# V01.net
KiCad netlist of a schematic drawn in EAGLE
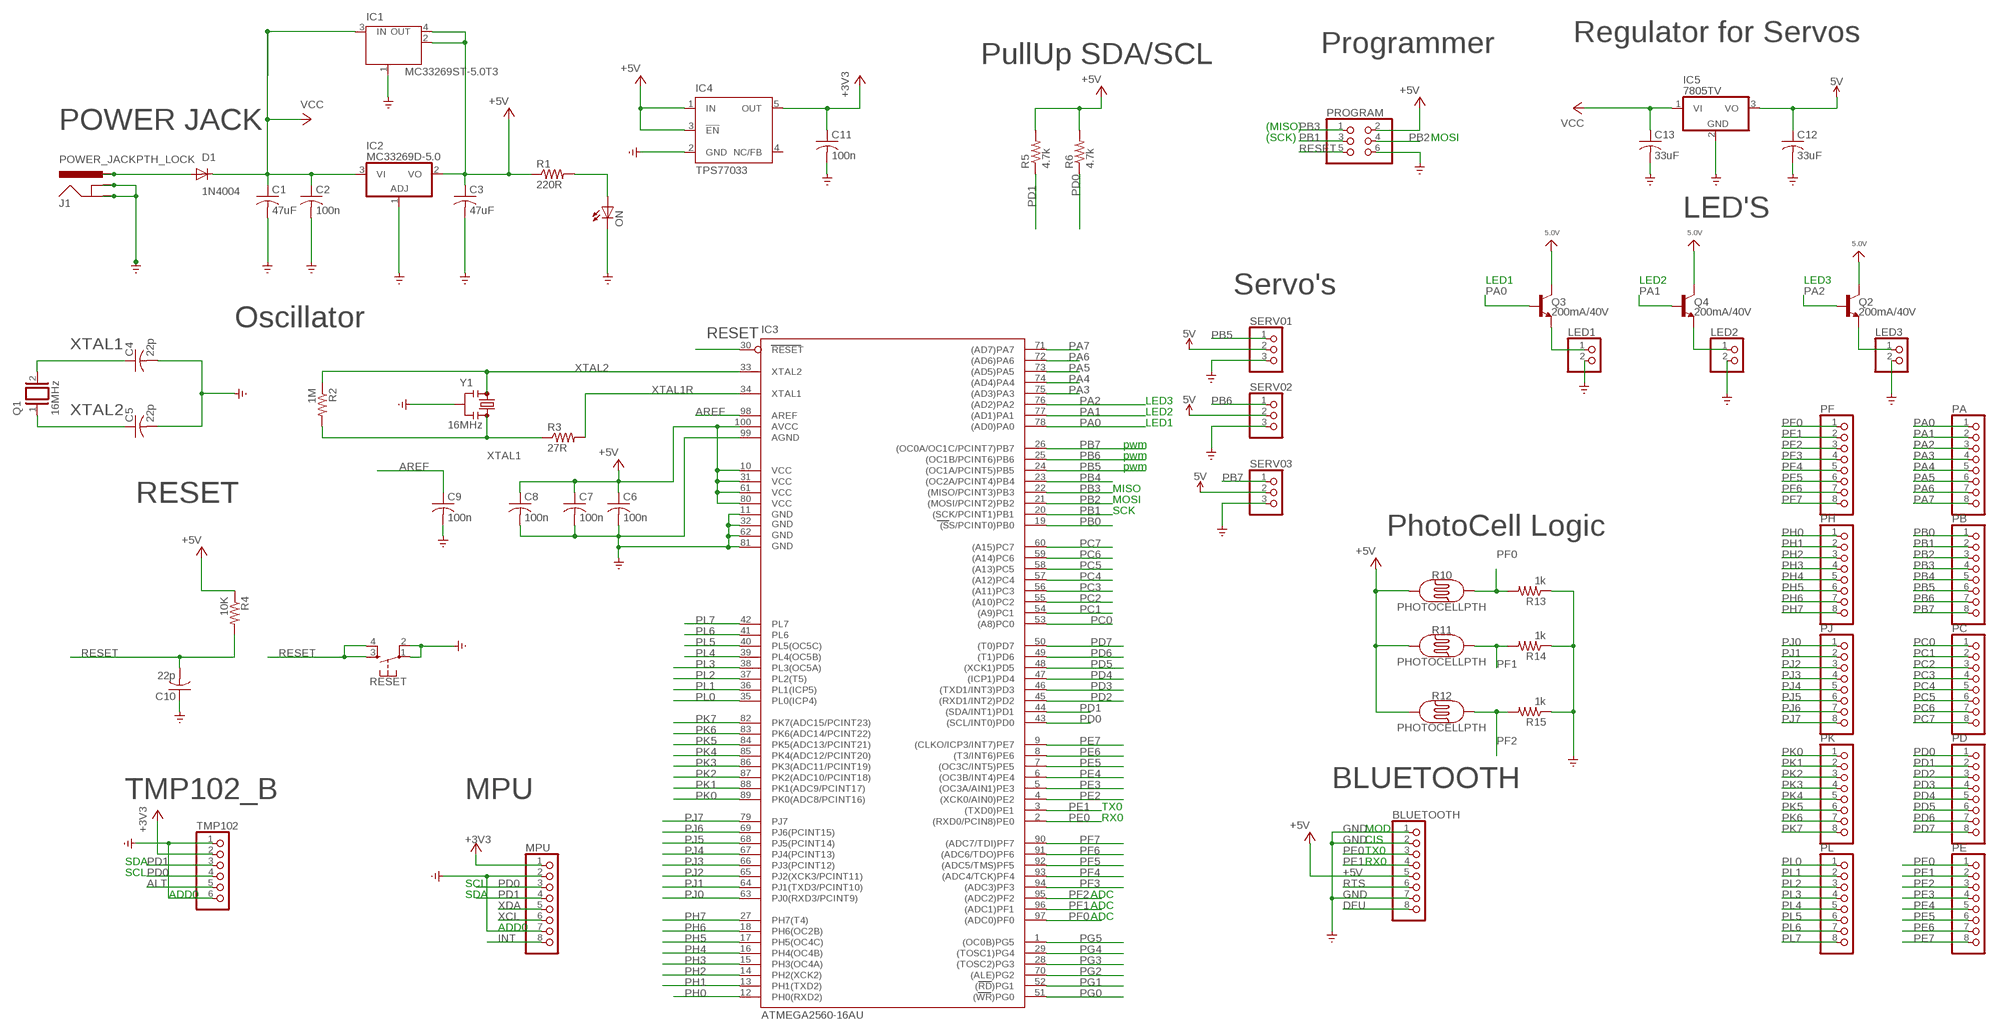
[diagram p0: schematic, sheet 1, part 1 of 2]
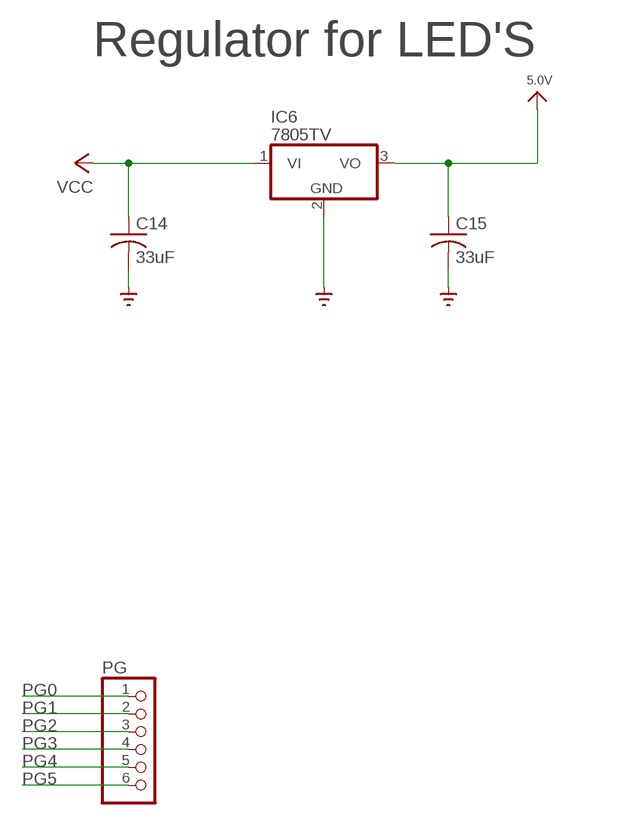
[diagram p1: schematic, sheet 1, part 2 of 2]

(export (version "E")
  (design (tool "Eeschema 10.0.6"))
  (components
    (comp (ref "BLUETOOTH")
      (value "PINHD-1X8")
      (footprint "eagle-import:1X08")
      (libsource (lib "eagle-import") (part "PINHD-1X8"))
    )
    (comp (ref "C1")
      (value "47uF")
      (footprint "eagle-import:C025-024X044")
      (libsource (lib "eagle-import") (part "C-US025-024X044"))
    )
    (comp (ref "C2")
      (value "100n")
      (footprint "eagle-import:C025-024X044")
      (libsource (lib "eagle-import") (part "C-US025-024X044"))
    )
    (comp (ref "C3")
      (value "47uF")
      (footprint "eagle-import:C025-024X044")
      (libsource (lib "eagle-import") (part "C-US025-024X044"))
    )
    (comp (ref "C4")
      (value "22p")
      (footprint "eagle-import:C025-024X044")
      (libsource (lib "eagle-import") (part "C-US025-024X044"))
    )
    (comp (ref "C5")
      (value "22p")
      (footprint "eagle-import:C025-024X044")
      (libsource (lib "eagle-import") (part "C-US025-024X044"))
    )
    (comp (ref "C6")
      (value "100n")
      (footprint "eagle-import:C025-024X044")
      (libsource (lib "eagle-import") (part "C-US025-024X044"))
    )
    (comp (ref "C7")
      (value "100n")
      (footprint "eagle-import:C025-024X044")
      (libsource (lib "eagle-import") (part "C-US025-024X044"))
    )
    (comp (ref "C8")
      (value "100n")
      (footprint "eagle-import:C025-024X044")
      (libsource (lib "eagle-import") (part "C-US025-024X044"))
    )
    (comp (ref "C9")
      (value "100n")
      (footprint "eagle-import:C025-024X044")
      (libsource (lib "eagle-import") (part "C-US025-024X044"))
    )
    (comp (ref "C10")
      (value "22p")
      (footprint "eagle-import:C025-024X044")
      (libsource (lib "eagle-import") (part "C-US025-024X044"))
    )
    (comp (ref "C11")
      (value "100n")
      (footprint "eagle-import:C025-024X044")
      (libsource (lib "eagle-import") (part "C-US025-024X044"))
    )
    (comp (ref "C12")
      (value "33uF")
      (footprint "eagle-import:C025-024X044")
      (libsource (lib "eagle-import") (part "C-US025-024X044"))
    )
    (comp (ref "C13")
      (value "33uF")
      (footprint "eagle-import:C025-024X044")
      (libsource (lib "eagle-import") (part "C-US025-024X044"))
    )
    (comp (ref "C14")
      (value "33uF")
      (footprint "eagle-import:C025-024X044")
      (libsource (lib "eagle-import") (part "C-US025-024X044"))
    )
    (comp (ref "C15")
      (value "33uF")
      (footprint "eagle-import:C025-024X044")
      (libsource (lib "eagle-import") (part "C-US025-024X044"))
    )
    (comp (ref "D1")
      (value "1N4004")
      (footprint "eagle-import:DO41-10")
      (libsource (lib "eagle-import") (part "1N4004"))
    )
    (comp (ref "IC1")
      (value "MC33269ST-5.0T3")
      (footprint "eagle-import:SOT223")
      (libsource (lib "eagle-import") (part "MC33269ST-3.3T3"))
    )
    (comp (ref "IC2")
      (value "MC33269D-5.0")
      (footprint "eagle-import:DPACK")
      (libsource (lib "eagle-import") (part "MC33269?D-5.0"))
    )
    (comp (ref "IC3")
      (value "ATMEGA2560-16AU")
      (footprint "eagle-import:TQFP100")
      (libsource (lib "eagle-import") (part "ATMEGAAU2560-16"))
    )
    (comp (ref "IC4")
      (value "TPS77033")
      (footprint "eagle-import:SOT23-DBV")
      (fields (field (name "MF") "TEXAS INSTRUMENTS") (field (name "MPN") "TPS77033DBVT"))
      (libsource (lib "eagle-import") (part "TPS77033"))
    )
    (comp (ref "IC5")
      (value "7805TV")
      (footprint "eagle-import:TO220V")
      (libsource (lib "eagle-import") (part "78TV05"))
    )
    (comp (ref "IC6")
      (value "7805TV")
      (footprint "eagle-import:TO220V")
      (libsource (lib "eagle-import") (part "78TV05"))
    )
    (comp (ref "J1")
      (value "POWER_JACKPTH_LOCK")
      (footprint "eagle-import:POWER_JACK_PTH_LOCK")
      (libsource (lib "eagle-import") (part "POWER_JACKPTH_LOCK"))
    )
    (comp (ref "LED1")
      (value "PINHD-1X2")
      (footprint "eagle-import:1X02")
      (libsource (lib "eagle-import") (part "PINHD-1X2"))
    )
    (comp (ref "LED2")
      (value "PINHD-1X2")
      (footprint "eagle-import:1X02")
      (libsource (lib "eagle-import") (part "PINHD-1X2"))
    )
    (comp (ref "LED3")
      (value "PINHD-1X2")
      (footprint "eagle-import:1X02")
      (libsource (lib "eagle-import") (part "PINHD-1X2"))
    )
    (comp (ref "MPU")
      (value "PINHD-1X8")
      (footprint "eagle-import:1X08")
      (libsource (lib "eagle-import") (part "PINHD-1X8"))
    )
    (comp (ref "ON")
      (value "LED3MM")
      (footprint "eagle-import:LED3MM")
      (libsource (lib "eagle-import") (part "LED3MM"))
    )
    (comp (ref "PA")
      (value "PINHD-1X8")
      (footprint "eagle-import:1X08")
      (libsource (lib "eagle-import") (part "PINHD-1X8"))
    )
    (comp (ref "PB")
      (value "PINHD-1X8")
      (footprint "eagle-import:1X08")
      (libsource (lib "eagle-import") (part "PINHD-1X8"))
    )
    (comp (ref "PC")
      (value "PINHD-1X8")
      (footprint "eagle-import:1X08")
      (libsource (lib "eagle-import") (part "PINHD-1X8"))
    )
    (comp (ref "PD")
      (value "PINHD-1X8")
      (footprint "eagle-import:1X08")
      (libsource (lib "eagle-import") (part "PINHD-1X8"))
    )
    (comp (ref "PE")
      (value "PINHD-1X8")
      (footprint "eagle-import:1X08")
      (libsource (lib "eagle-import") (part "PINHD-1X8"))
    )
    (comp (ref "PF")
      (value "PINHD-1X8")
      (footprint "eagle-import:1X08")
      (libsource (lib "eagle-import") (part "PINHD-1X8"))
    )
    (comp (ref "PG")
      (value "PINHD-1X6")
      (footprint "eagle-import:1X06")
      (libsource (lib "eagle-import") (part "PINHD-1X6"))
    )
    (comp (ref "PH")
      (value "PINHD-1X8")
      (footprint "eagle-import:1X08")
      (libsource (lib "eagle-import") (part "PINHD-1X8"))
    )
    (comp (ref "PJ")
      (value "PINHD-1X8")
      (footprint "eagle-import:1X08")
      (libsource (lib "eagle-import") (part "PINHD-1X8"))
    )
    (comp (ref "PK")
      (value "PINHD-1X8")
      (footprint "eagle-import:1X08")
      (libsource (lib "eagle-import") (part "PINHD-1X8"))
    )
    (comp (ref "PL")
      (value "PINHD-1X8")
      (footprint "eagle-import:1X08")
      (libsource (lib "eagle-import") (part "PINHD-1X8"))
    )
    (comp (ref "PROGRAM")
      (value "PINHD-2X3")
      (footprint "eagle-import:2X03")
      (libsource (lib "eagle-import") (part "PINHD-2X3"))
    )
    (comp (ref "Q1")
      (value "16MHz")
      (footprint "eagle-import:QS")
      (libsource (lib "eagle-import") (part "XTAL/S"))
    )
    (comp (ref "Q2")
      (value "200mA/40V")
      (footprint "eagle-import:TO-92")
      (libsource (lib "eagle-import") (part "TRANS_NPN-2N3904"))
    )
    (comp (ref "Q3")
      (value "200mA/40V")
      (footprint "eagle-import:TO-92")
      (libsource (lib "eagle-import") (part "TRANS_NPN-2N3904"))
    )
    (comp (ref "Q4")
      (value "200mA/40V")
      (footprint "eagle-import:TO-92")
      (libsource (lib "eagle-import") (part "TRANS_NPN-2N3904"))
    )
    (comp (ref "R1")
      (value "220R")
      (footprint "eagle-import:0204V")
      (libsource (lib "eagle-import") (part "R-US_0204/2V"))
    )
    (comp (ref "R2")
      (value "1M")
      (footprint "eagle-import:0204V")
      (libsource (lib "eagle-import") (part "R-US_0204/2V"))
    )
    (comp (ref "R3")
      (value "27R")
      (footprint "eagle-import:0204V")
      (libsource (lib "eagle-import") (part "R-US_0204/2V"))
    )
    (comp (ref "R4")
      (value "10K")
      (footprint "eagle-import:0204V")
      (libsource (lib "eagle-import") (part "R-US_0204/2V"))
    )
    (comp (ref "R5")
      (value "4.7k")
      (footprint "eagle-import:0204V")
      (libsource (lib "eagle-import") (part "R-US_0204/2V"))
    )
    (comp (ref "R6")
      (value "4.7k")
      (footprint "eagle-import:0204V")
      (libsource (lib "eagle-import") (part "R-US_0204/2V"))
    )
    (comp (ref "R10")
      (value "PHOTOCELLPTH")
      (footprint "eagle-import:PHOTOCELL")
      (libsource (lib "eagle-import") (part "PHOTOCELLPTH"))
    )
    (comp (ref "R11")
      (value "PHOTOCELLPTH")
      (footprint "eagle-import:PHOTOCELL")
      (libsource (lib "eagle-import") (part "PHOTOCELLPTH"))
    )
    (comp (ref "R12")
      (value "PHOTOCELLPTH")
      (footprint "eagle-import:PHOTOCELL")
      (libsource (lib "eagle-import") (part "PHOTOCELLPTH"))
    )
    (comp (ref "R13")
      (value "1k")
      (footprint "eagle-import:0204V")
      (libsource (lib "eagle-import") (part "R-US_0204/2V"))
    )
    (comp (ref "R14")
      (value "1k")
      (footprint "eagle-import:0204V")
      (libsource (lib "eagle-import") (part "R-US_0204/2V"))
    )
    (comp (ref "R15")
      (value "1k")
      (footprint "eagle-import:0204V")
      (libsource (lib "eagle-import") (part "R-US_0204/2V"))
    )
    (comp (ref "RESET")
      (value "MOMENTARY-SWITCH-SPST-2-SMD-5.2MM")
      (footprint "eagle-import:TACTILE_SWITCH_SMD_5.2MM")
      (libsource (lib "eagle-import") (part "MOMENTARY-SWITCH-SPST-2-SMD-5.2MM"))
    )
    (comp (ref "SERV01")
      (value "PINHD-1X3")
      (footprint "eagle-import:1X03")
      (libsource (lib "eagle-import") (part "PINHD-1X3"))
    )
    (comp (ref "SERV02")
      (value "PINHD-1X3")
      (footprint "eagle-import:1X03")
      (libsource (lib "eagle-import") (part "PINHD-1X3"))
    )
    (comp (ref "SERV03")
      (value "PINHD-1X3")
      (footprint "eagle-import:1X03")
      (libsource (lib "eagle-import") (part "PINHD-1X3"))
    )
    (comp (ref "TMP102")
      (value "PINHD-1X6")
      (footprint "eagle-import:1X06")
      (libsource (lib "eagle-import") (part "PINHD-1X6"))
    )
    (comp (ref "Y1")
      (value "16MHz")
      (footprint "eagle-import:RESONATOR-SMD-3.2X1.3")
      (libsource (lib "eagle-import") (part "RESONATORSMD-3.2X1.3"))
    )
  )
  (nets
    (net (code "1") (name "+3V3") (class "Default")
      (node (ref "C11") (pin "1") (pinfunction "1_1") (pintype "passive"))
      (node (ref "IC4") (pin "5") (pinfunction "OUT_5") (pintype "passive"))
      (node (ref "MPU") (pin "1") (pinfunction "1_1") (pintype "passive"))
      (node (ref "TMP102") (pin "2") (pinfunction "2_2") (pintype "passive"))
    )
    (net (code "2") (name "+5V") (class "Default")
      (node (ref "BLUETOOTH") (pin "5") (pinfunction "5_5") (pintype "passive"))
      (node (ref "C3") (pin "1") (pinfunction "1_1") (pintype "passive"))
      (node (ref "C6") (pin "1") (pinfunction "1_1") (pintype "passive"))
      (node (ref "C7") (pin "1") (pinfunction "1_1") (pintype "passive"))
      (node (ref "C8") (pin "1") (pinfunction "1_1") (pintype "passive"))
      (node (ref "IC1") (pin "2") (pinfunction "OUT_2") (pintype "passive"))
      (node (ref "IC1") (pin "4") (pinfunction "OUT_4") (pintype "passive"))
      (node (ref "IC2") (pin "2") (pinfunction "VO_2") (pintype "passive"))
      (node (ref "IC3") (pin "10") (pinfunction "VCC_10") (pintype "power_in"))
      (node (ref "IC3") (pin "100") (pinfunction "AVCC_100") (pintype "power_in"))
      (node (ref "IC3") (pin "31") (pinfunction "VCC1_31") (pintype "power_in"))
      (node (ref "IC3") (pin "61") (pinfunction "VCC2_61") (pintype "power_in"))
      (node (ref "IC3") (pin "80") (pinfunction "VCC3_80") (pintype "power_in"))
      (node (ref "IC4") (pin "1") (pinfunction "IN_1") (pintype "input"))
      (node (ref "IC4") (pin "3") (pinfunction "~{EN}_3") (pintype "input"))
      (node (ref "PROGRAM") (pin "2") (pinfunction "2_2") (pintype "passive"))
      (node (ref "R1") (pin "1") (pinfunction "1_1") (pintype "passive"))
      (node (ref "R10") (pin "1") (pinfunction "P$1_1") (pintype "bidirectional"))
      (node (ref "R11") (pin "1") (pinfunction "P$1_1") (pintype "bidirectional"))
      (node (ref "R12") (pin "1") (pinfunction "P$1_1") (pintype "bidirectional"))
      (node (ref "R4") (pin "1") (pinfunction "1_1") (pintype "passive"))
      (node (ref "R5") (pin "2") (pinfunction "2_2") (pintype "passive"))
      (node (ref "R6") (pin "2") (pinfunction "2_2") (pintype "passive"))
    )
    (net (code "3") (name "/ALT") (class "Default")
      (node (ref "TMP102") (pin "5") (pinfunction "5_5") (pintype "passive"))
    )
    (net (code "4") (name "/AREF") (class "Default")
      (node (ref "C9") (pin "1") (pinfunction "1_1") (pintype "passive"))
      (node (ref "IC3") (pin "98") (pinfunction "AREF_98") (pintype "bidirectional"))
    )
    (net (code "5") (name "/DFU") (class "Default")
      (node (ref "BLUETOOTH") (pin "8") (pinfunction "8_8") (pintype "passive"))
    )
    (net (code "6") (name "/INT") (class "Default")
      (node (ref "MPU") (pin "8") (pinfunction "8_8") (pintype "passive"))
    )
    (net (code "7") (name "/PA0") (class "Default")
      (node (ref "IC3") (pin "78") (pinfunction "(AD0)PA0_78") (pintype "bidirectional"))
      (node (ref "PA") (pin "1") (pinfunction "1_1") (pintype "passive"))
      (node (ref "Q3") (pin "2") (pinfunction "B_2") (pintype "passive"))
    )
    (net (code "8") (name "/PA1") (class "Default")
      (node (ref "IC3") (pin "77") (pinfunction "(AD1)PA1_77") (pintype "bidirectional"))
      (node (ref "PA") (pin "2") (pinfunction "2_2") (pintype "passive"))
      (node (ref "Q4") (pin "2") (pinfunction "B_2") (pintype "passive"))
    )
    (net (code "9") (name "/PA2") (class "Default")
      (node (ref "IC3") (pin "76") (pinfunction "(AD2)PA2_76") (pintype "bidirectional"))
      (node (ref "PA") (pin "3") (pinfunction "3_3") (pintype "passive"))
      (node (ref "Q2") (pin "2") (pinfunction "B_2") (pintype "passive"))
    )
    (net (code "10") (name "/PA3") (class "Default")
      (node (ref "IC3") (pin "75") (pinfunction "(AD3)PA3_75") (pintype "bidirectional"))
      (node (ref "PA") (pin "4") (pinfunction "4_4") (pintype "passive"))
    )
    (net (code "11") (name "/PA4") (class "Default")
      (node (ref "IC3") (pin "74") (pinfunction "(AD4)PA4_74") (pintype "bidirectional"))
      (node (ref "PA") (pin "5") (pinfunction "5_5") (pintype "passive"))
    )
    (net (code "12") (name "/PA5") (class "Default")
      (node (ref "IC3") (pin "73") (pinfunction "(AD5)PA5_73") (pintype "bidirectional"))
      (node (ref "PA") (pin "6") (pinfunction "6_6") (pintype "passive"))
    )
    (net (code "13") (name "/PA6") (class "Default")
      (node (ref "IC3") (pin "72") (pinfunction "(AD6)PA6_72") (pintype "bidirectional"))
      (node (ref "PA") (pin "7") (pinfunction "7_7") (pintype "passive"))
    )
    (net (code "14") (name "/PA7") (class "Default")
      (node (ref "IC3") (pin "71") (pinfunction "(AD7)PA7_71") (pintype "bidirectional"))
      (node (ref "PA") (pin "8") (pinfunction "8_8") (pintype "passive"))
    )
    (net (code "15") (name "/PB0") (class "Default")
      (node (ref "IC3") (pin "19") (pinfunction "(SS/PCINT0)PB0_19") (pintype "bidirectional"))
      (node (ref "PB") (pin "1") (pinfunction "1_1") (pintype "passive"))
    )
    (net (code "16") (name "/PB1") (class "Default")
      (node (ref "IC3") (pin "20") (pinfunction "(SCK/PCINT1)PB1_20") (pintype "bidirectional"))
      (node (ref "PB") (pin "2") (pinfunction "2_2") (pintype "passive"))
      (node (ref "PROGRAM") (pin "3") (pinfunction "3_3") (pintype "passive"))
    )
    (net (code "17") (name "/PB2") (class "Default")
      (node (ref "IC3") (pin "21") (pinfunction "(MOSI/PCINT2)PB2_21") (pintype "bidirectional"))
      (node (ref "PB") (pin "3") (pinfunction "3_3") (pintype "passive"))
      (node (ref "PROGRAM") (pin "4") (pinfunction "4_4") (pintype "passive"))
    )
    (net (code "18") (name "/PB3") (class "Default")
      (node (ref "IC3") (pin "22") (pinfunction "(MISO/PCINT3)PB3_22") (pintype "bidirectional"))
      (node (ref "PB") (pin "4") (pinfunction "4_4") (pintype "passive"))
      (node (ref "PROGRAM") (pin "1") (pinfunction "1_1") (pintype "passive"))
    )
    (net (code "19") (name "/PB4") (class "Default")
      (node (ref "IC3") (pin "23") (pinfunction "(OC2A/PCINT4)PB4_23") (pintype "bidirectional"))
      (node (ref "PB") (pin "5") (pinfunction "5_5") (pintype "passive"))
    )
    (net (code "20") (name "/PB5") (class "Default")
      (node (ref "IC3") (pin "24") (pinfunction "(OC1A/PCINT5)PB5_24") (pintype "bidirectional"))
      (node (ref "PB") (pin "6") (pinfunction "6_6") (pintype "passive"))
      (node (ref "SERV01") (pin "1") (pinfunction "1_1") (pintype "passive"))
    )
    (net (code "21") (name "/PB6") (class "Default")
      (node (ref "IC3") (pin "25") (pinfunction "(OC1B/PCINT6)PB6_25") (pintype "bidirectional"))
      (node (ref "PB") (pin "7") (pinfunction "7_7") (pintype "passive"))
      (node (ref "SERV02") (pin "1") (pinfunction "1_1") (pintype "passive"))
    )
    (net (code "22") (name "/PB7") (class "Default")
      (node (ref "IC3") (pin "26") (pinfunction "(OC0A/OC1C/PCINT7)PB7_26") (pintype "bidirectional"))
      (node (ref "PB") (pin "8") (pinfunction "8_8") (pintype "passive"))
      (node (ref "SERV03") (pin "1") (pinfunction "1_1") (pintype "passive"))
    )
    (net (code "23") (name "/PC0") (class "Default")
      (node (ref "IC3") (pin "53") (pinfunction "(A8)PC0_53") (pintype "bidirectional"))
      (node (ref "PC") (pin "1") (pinfunction "1_1") (pintype "passive"))
    )
    (net (code "24") (name "/PC1") (class "Default")
      (node (ref "IC3") (pin "54") (pinfunction "(A9)PC1_54") (pintype "bidirectional"))
      (node (ref "PC") (pin "2") (pinfunction "2_2") (pintype "passive"))
    )
    (net (code "25") (name "/PC2") (class "Default")
      (node (ref "IC3") (pin "55") (pinfunction "(A10)PC2_55") (pintype "bidirectional"))
      (node (ref "PC") (pin "3") (pinfunction "3_3") (pintype "passive"))
    )
    (net (code "26") (name "/PC3") (class "Default")
      (node (ref "IC3") (pin "56") (pinfunction "(A11)PC3_56") (pintype "bidirectional"))
      (node (ref "PC") (pin "4") (pinfunction "4_4") (pintype "passive"))
    )
    (net (code "27") (name "/PC4") (class "Default")
      (node (ref "IC3") (pin "57") (pinfunction "(A12)PC4_57") (pintype "bidirectional"))
      (node (ref "PC") (pin "5") (pinfunction "5_5") (pintype "passive"))
    )
    (net (code "28") (name "/PC5") (class "Default")
      (node (ref "IC3") (pin "58") (pinfunction "(A13)PC5_58") (pintype "bidirectional"))
      (node (ref "PC") (pin "6") (pinfunction "6_6") (pintype "passive"))
    )
    (net (code "29") (name "/PC6") (class "Default")
      (node (ref "IC3") (pin "59") (pinfunction "(A14)PC6_59") (pintype "bidirectional"))
      (node (ref "PC") (pin "7") (pinfunction "7_7") (pintype "passive"))
    )
    (net (code "30") (name "/PC7") (class "Default")
      (node (ref "IC3") (pin "60") (pinfunction "(A15)PC7_60") (pintype "bidirectional"))
      (node (ref "PC") (pin "8") (pinfunction "8_8") (pintype "passive"))
    )
    (net (code "31") (name "/PD0") (class "Default")
      (node (ref "IC3") (pin "43") (pinfunction "(SCL/INT0)PD0_43") (pintype "bidirectional"))
      (node (ref "MPU") (pin "3") (pinfunction "3_3") (pintype "passive"))
      (node (ref "PD") (pin "1") (pinfunction "1_1") (pintype "passive"))
      (node (ref "R6") (pin "1") (pinfunction "1_1") (pintype "passive"))
      (node (ref "TMP102") (pin "4") (pinfunction "4_4") (pintype "passive"))
    )
    (net (code "32") (name "/PD1") (class "Default")
      (node (ref "IC3") (pin "44") (pinfunction "(SDA/INT1)PD1_44") (pintype "bidirectional"))
      (node (ref "MPU") (pin "4") (pinfunction "4_4") (pintype "passive"))
      (node (ref "PD") (pin "2") (pinfunction "2_2") (pintype "passive"))
      (node (ref "R5") (pin "1") (pinfunction "1_1") (pintype "passive"))
      (node (ref "TMP102") (pin "3") (pinfunction "3_3") (pintype "passive"))
    )
    (net (code "33") (name "/PD2") (class "Default")
      (node (ref "IC3") (pin "45") (pinfunction "(RXD1/INT2)PD2_45") (pintype "bidirectional"))
      (node (ref "PD") (pin "3") (pinfunction "3_3") (pintype "passive"))
    )
    (net (code "34") (name "/PD3") (class "Default")
      (node (ref "IC3") (pin "46") (pinfunction "(TXD1/INT3)PD3_46") (pintype "bidirectional"))
      (node (ref "PD") (pin "4") (pinfunction "4_4") (pintype "passive"))
    )
    (net (code "35") (name "/PD4") (class "Default")
      (node (ref "IC3") (pin "47") (pinfunction "(ICP1)PD4_47") (pintype "bidirectional"))
      (node (ref "PD") (pin "5") (pinfunction "5_5") (pintype "passive"))
    )
    (net (code "36") (name "/PD5") (class "Default")
      (node (ref "IC3") (pin "48") (pinfunction "(XCK1)PD5_48") (pintype "bidirectional"))
      (node (ref "PD") (pin "6") (pinfunction "6_6") (pintype "passive"))
    )
    (net (code "37") (name "/PD6") (class "Default")
      (node (ref "IC3") (pin "49") (pinfunction "(T1)PD6_49") (pintype "bidirectional"))
      (node (ref "PD") (pin "7") (pinfunction "7_7") (pintype "passive"))
    )
    (net (code "38") (name "/PD7") (class "Default")
      (node (ref "IC3") (pin "50") (pinfunction "(T0)PD7_50") (pintype "bidirectional"))
      (node (ref "PD") (pin "8") (pinfunction "8_8") (pintype "passive"))
    )
    (net (code "39") (name "/PE0") (class "Default")
      (node (ref "BLUETOOTH") (pin "3") (pinfunction "3_3") (pintype "passive"))
      (node (ref "IC3") (pin "2") (pinfunction "(RXD0/PCIN8)PE0_2") (pintype "bidirectional"))
      (node (ref "PE") (pin "1") (pinfunction "1_1") (pintype "passive"))
    )
    (net (code "40") (name "/PE1") (class "Default")
      (node (ref "BLUETOOTH") (pin "4") (pinfunction "4_4") (pintype "passive"))
      (node (ref "IC3") (pin "3") (pinfunction "(TXD0)PE1_3") (pintype "bidirectional"))
      (node (ref "PE") (pin "2") (pinfunction "2_2") (pintype "passive"))
    )
    (net (code "41") (name "/PE2") (class "Default")
      (node (ref "IC3") (pin "4") (pinfunction "(XCK0/AIN0)PE2_4") (pintype "bidirectional"))
      (node (ref "PE") (pin "3") (pinfunction "3_3") (pintype "passive"))
    )
    (net (code "42") (name "/PE3") (class "Default")
      (node (ref "IC3") (pin "5") (pinfunction "(OC3A/AIN1)PE3_5") (pintype "bidirectional"))
      (node (ref "PE") (pin "4") (pinfunction "4_4") (pintype "passive"))
    )
    (net (code "43") (name "/PE4") (class "Default")
      (node (ref "IC3") (pin "6") (pinfunction "(OC3B/INT4)PE4_6") (pintype "bidirectional"))
      (node (ref "PE") (pin "5") (pinfunction "5_5") (pintype "passive"))
    )
    (net (code "44") (name "/PE5") (class "Default")
      (node (ref "IC3") (pin "7") (pinfunction "(OC3C/INT5)PE5_7") (pintype "bidirectional"))
      (node (ref "PE") (pin "6") (pinfunction "6_6") (pintype "passive"))
    )
    (net (code "45") (name "/PE6") (class "Default")
      (node (ref "IC3") (pin "8") (pinfunction "(T3/INT6)PE6_8") (pintype "bidirectional"))
      (node (ref "PE") (pin "7") (pinfunction "7_7") (pintype "passive"))
    )
    (net (code "46") (name "/PE7") (class "Default")
      (node (ref "IC3") (pin "9") (pinfunction "(CLKO/ICP3/INT7)PE7_9") (pintype "bidirectional"))
      (node (ref "PE") (pin "8") (pinfunction "8_8") (pintype "passive"))
    )
    (net (code "47") (name "/PF0") (class "Default")
      (node (ref "IC3") (pin "97") (pinfunction "(ADC0)PF0_97") (pintype "bidirectional"))
      (node (ref "PF") (pin "1") (pinfunction "1_1") (pintype "passive"))
      (node (ref "R10") (pin "2") (pinfunction "P$2_2") (pintype "bidirectional"))
      (node (ref "R13") (pin "2") (pinfunction "2_2") (pintype "passive"))
    )
    (net (code "48") (name "/PF1") (class "Default")
      (node (ref "IC3") (pin "96") (pinfunction "(ADC1)PF1_96") (pintype "bidirectional"))
      (node (ref "PF") (pin "2") (pinfunction "2_2") (pintype "passive"))
      (node (ref "R11") (pin "2") (pinfunction "P$2_2") (pintype "bidirectional"))
      (node (ref "R14") (pin "2") (pinfunction "2_2") (pintype "passive"))
    )
    (net (code "49") (name "/PF2") (class "Default")
      (node (ref "IC3") (pin "95") (pinfunction "(ADC2)PF2_95") (pintype "bidirectional"))
      (node (ref "PF") (pin "3") (pinfunction "3_3") (pintype "passive"))
      (node (ref "R12") (pin "2") (pinfunction "P$2_2") (pintype "bidirectional"))
      (node (ref "R15") (pin "2") (pinfunction "2_2") (pintype "passive"))
    )
    (net (code "50") (name "/PF3") (class "Default")
      (node (ref "IC3") (pin "94") (pinfunction "(ADC3)PF3_94") (pintype "bidirectional"))
      (node (ref "PF") (pin "4") (pinfunction "4_4") (pintype "passive"))
    )
    (net (code "51") (name "/PF4") (class "Default")
      (node (ref "IC3") (pin "93") (pinfunction "(ADC4/TCK)PF4_93") (pintype "bidirectional"))
      (node (ref "PF") (pin "5") (pinfunction "5_5") (pintype "passive"))
    )
    (net (code "52") (name "/PF5") (class "Default")
      (node (ref "IC3") (pin "92") (pinfunction "(ADC5/TMS)PF5_92") (pintype "bidirectional"))
      (node (ref "PF") (pin "6") (pinfunction "6_6") (pintype "passive"))
    )
    (net (code "53") (name "/PF6") (class "Default")
      (node (ref "IC3") (pin "91") (pinfunction "(ADC6/TDO)PF6_91") (pintype "bidirectional"))
      (node (ref "PF") (pin "7") (pinfunction "7_7") (pintype "passive"))
    )
    (net (code "54") (name "/PF7") (class "Default")
      (node (ref "IC3") (pin "90") (pinfunction "(ADC7/TDI)PF7_90") (pintype "bidirectional"))
      (node (ref "PF") (pin "8") (pinfunction "8_8") (pintype "passive"))
    )
    (net (code "55") (name "/PG0") (class "Default")
      (node (ref "IC3") (pin "51") (pinfunction "(WR)PG0_51") (pintype "bidirectional"))
      (node (ref "PG") (pin "1") (pinfunction "1_1") (pintype "passive"))
    )
    (net (code "56") (name "/PG1") (class "Default")
      (node (ref "IC3") (pin "52") (pinfunction "(RD)PG1_52") (pintype "bidirectional"))
      (node (ref "PG") (pin "2") (pinfunction "2_2") (pintype "passive"))
    )
    (net (code "57") (name "/PG2") (class "Default")
      (node (ref "IC3") (pin "70") (pinfunction "(ALE)PG2_70") (pintype "bidirectional"))
      (node (ref "PG") (pin "3") (pinfunction "3_3") (pintype "passive"))
    )
    (net (code "58") (name "/PG3") (class "Default")
      (node (ref "IC3") (pin "28") (pinfunction "(TOSC2)PG3_28") (pintype "bidirectional"))
      (node (ref "PG") (pin "4") (pinfunction "4_4") (pintype "passive"))
    )
    (net (code "59") (name "/PG4") (class "Default")
      (node (ref "IC3") (pin "29") (pinfunction "(TOSC1)PG4_29") (pintype "bidirectional"))
      (node (ref "PG") (pin "5") (pinfunction "5_5") (pintype "passive"))
    )
    (net (code "60") (name "/PG5") (class "Default")
      (node (ref "IC3") (pin "1") (pinfunction "(OC0B)PG5_1") (pintype "bidirectional"))
      (node (ref "PG") (pin "6") (pinfunction "6_6") (pintype "passive"))
    )
    (net (code "61") (name "/PH0") (class "Default")
      (node (ref "IC3") (pin "12") (pinfunction "PH0(RXD2)_12") (pintype "bidirectional"))
      (node (ref "PH") (pin "1") (pinfunction "1_1") (pintype "passive"))
    )
    (net (code "62") (name "/PH1") (class "Default")
      (node (ref "IC3") (pin "13") (pinfunction "PH1(TXD2)_13") (pintype "bidirectional"))
      (node (ref "PH") (pin "2") (pinfunction "2_2") (pintype "passive"))
    )
    (net (code "63") (name "/PH2") (class "Default")
      (node (ref "IC3") (pin "14") (pinfunction "PH2(XCK2)_14") (pintype "bidirectional"))
      (node (ref "PH") (pin "3") (pinfunction "3_3") (pintype "passive"))
    )
    (net (code "64") (name "/PH3") (class "Default")
      (node (ref "IC3") (pin "15") (pinfunction "PH3(OC4A)_15") (pintype "bidirectional"))
      (node (ref "PH") (pin "4") (pinfunction "4_4") (pintype "passive"))
    )
    (net (code "65") (name "/PH4") (class "Default")
      (node (ref "IC3") (pin "16") (pinfunction "PH4(OC4B)_16") (pintype "bidirectional"))
      (node (ref "PH") (pin "5") (pinfunction "5_5") (pintype "passive"))
    )
    (net (code "66") (name "/PH5") (class "Default")
      (node (ref "IC3") (pin "17") (pinfunction "PH5(OC4C)_17") (pintype "bidirectional"))
      (node (ref "PH") (pin "6") (pinfunction "6_6") (pintype "passive"))
    )
    (net (code "67") (name "/PH6") (class "Default")
      (node (ref "IC3") (pin "18") (pinfunction "PH6(OC2B)_18") (pintype "bidirectional"))
      (node (ref "PH") (pin "7") (pinfunction "7_7") (pintype "passive"))
    )
    (net (code "68") (name "/PH7") (class "Default")
      (node (ref "IC3") (pin "27") (pinfunction "PH7(T4)_27") (pintype "bidirectional"))
      (node (ref "PH") (pin "8") (pinfunction "8_8") (pintype "passive"))
    )
    (net (code "69") (name "/PJ0") (class "Default")
      (node (ref "IC3") (pin "63") (pinfunction "PJ0(RXD3/PCINT9)_63") (pintype "bidirectional"))
      (node (ref "PJ") (pin "1") (pinfunction "1_1") (pintype "passive"))
    )
    (net (code "70") (name "/PJ1") (class "Default")
      (node (ref "IC3") (pin "64") (pinfunction "PJ1(TXD3/PCINT10)_64") (pintype "bidirectional"))
      (node (ref "PJ") (pin "2") (pinfunction "2_2") (pintype "passive"))
    )
    (net (code "71") (name "/PJ2") (class "Default")
      (node (ref "IC3") (pin "65") (pinfunction "PJ2(XCK3/PCINT11)_65") (pintype "bidirectional"))
      (node (ref "PJ") (pin "3") (pinfunction "3_3") (pintype "passive"))
    )
    (net (code "72") (name "/PJ3") (class "Default")
      (node (ref "IC3") (pin "66") (pinfunction "PJ3(PCINT12)_66") (pintype "bidirectional"))
      (node (ref "PJ") (pin "4") (pinfunction "4_4") (pintype "passive"))
    )
    (net (code "73") (name "/PJ4") (class "Default")
      (node (ref "IC3") (pin "67") (pinfunction "PJ4(PCINT13)_67") (pintype "bidirectional"))
      (node (ref "PJ") (pin "5") (pinfunction "5_5") (pintype "passive"))
    )
    (net (code "74") (name "/PJ5") (class "Default")
      (node (ref "IC3") (pin "68") (pinfunction "PJ5(PCINT14)_68") (pintype "bidirectional"))
      (node (ref "PJ") (pin "6") (pinfunction "6_6") (pintype "passive"))
    )
    (net (code "75") (name "/PJ6") (class "Default")
      (node (ref "IC3") (pin "69") (pinfunction "PJ6(PCINT15)_69") (pintype "bidirectional"))
      (node (ref "PJ") (pin "7") (pinfunction "7_7") (pintype "passive"))
    )
    (net (code "76") (name "/PJ7") (class "Default")
      (node (ref "IC3") (pin "79") (pinfunction "PJ7_79") (pintype "bidirectional"))
      (node (ref "PJ") (pin "8") (pinfunction "8_8") (pintype "passive"))
    )
    (net (code "77") (name "/PK0") (class "Default")
      (node (ref "IC3") (pin "89") (pinfunction "PK0(ADC8/PCINT16)_89") (pintype "bidirectional"))
      (node (ref "PK") (pin "1") (pinfunction "1_1") (pintype "passive"))
    )
    (net (code "78") (name "/PK1") (class "Default")
      (node (ref "IC3") (pin "88") (pinfunction "PK1(ADC9/PCINT17)_88") (pintype "bidirectional"))
      (node (ref "PK") (pin "2") (pinfunction "2_2") (pintype "passive"))
    )
    (net (code "79") (name "/PK2") (class "Default")
      (node (ref "IC3") (pin "87") (pinfunction "PK2(ADC10/PCINT18)_87") (pintype "bidirectional"))
      (node (ref "PK") (pin "3") (pinfunction "3_3") (pintype "passive"))
    )
    (net (code "80") (name "/PK3") (class "Default")
      (node (ref "IC3") (pin "86") (pinfunction "PK3(ADC11/PCINT19)_86") (pintype "bidirectional"))
      (node (ref "PK") (pin "4") (pinfunction "4_4") (pintype "passive"))
    )
    (net (code "81") (name "/PK4") (class "Default")
      (node (ref "IC3") (pin "85") (pinfunction "PK4(ADC12/PCINT20)_85") (pintype "bidirectional"))
      (node (ref "PK") (pin "5") (pinfunction "5_5") (pintype "passive"))
    )
    (net (code "82") (name "/PK5") (class "Default")
      (node (ref "IC3") (pin "84") (pinfunction "PK5(ADC13/PCINT21)_84") (pintype "bidirectional"))
      (node (ref "PK") (pin "6") (pinfunction "6_6") (pintype "passive"))
    )
    (net (code "83") (name "/PK6") (class "Default")
      (node (ref "IC3") (pin "83") (pinfunction "PK6(ADC14/PCINT22)_83") (pintype "bidirectional"))
      (node (ref "PK") (pin "7") (pinfunction "7_7") (pintype "passive"))
    )
    (net (code "84") (name "/PK7") (class "Default")
      (node (ref "IC3") (pin "82") (pinfunction "PK7(ADC15/PCINT23)_82") (pintype "bidirectional"))
      (node (ref "PK") (pin "8") (pinfunction "8_8") (pintype "passive"))
    )
    (net (code "85") (name "/PL0") (class "Default")
      (node (ref "IC3") (pin "35") (pinfunction "PL0(ICP4)_35") (pintype "bidirectional"))
      (node (ref "PL") (pin "1") (pinfunction "1_1") (pintype "passive"))
    )
    (net (code "86") (name "/PL1") (class "Default")
      (node (ref "IC3") (pin "36") (pinfunction "PL1(ICP5)_36") (pintype "bidirectional"))
      (node (ref "PL") (pin "2") (pinfunction "2_2") (pintype "passive"))
    )
    (net (code "87") (name "/PL2") (class "Default")
      (node (ref "IC3") (pin "37") (pinfunction "PL2(T5)_37") (pintype "bidirectional"))
      (node (ref "PL") (pin "3") (pinfunction "3_3") (pintype "passive"))
    )
    (net (code "88") (name "/PL3") (class "Default")
      (node (ref "IC3") (pin "38") (pinfunction "PL3(OC5A)_38") (pintype "bidirectional"))
      (node (ref "PL") (pin "4") (pinfunction "4_4") (pintype "passive"))
    )
    (net (code "89") (name "/PL4") (class "Default")
      (node (ref "IC3") (pin "39") (pinfunction "PL4(OC5B)_39") (pintype "bidirectional"))
      (node (ref "PL") (pin "5") (pinfunction "5_5") (pintype "passive"))
    )
    (net (code "90") (name "/PL5") (class "Default")
      (node (ref "IC3") (pin "40") (pinfunction "PL5(OC5C)_40") (pintype "bidirectional"))
      (node (ref "PL") (pin "6") (pinfunction "6_6") (pintype "passive"))
    )
    (net (code "91") (name "/PL6") (class "Default")
      (node (ref "IC3") (pin "41") (pinfunction "PL6_41") (pintype "bidirectional"))
      (node (ref "PL") (pin "7") (pinfunction "7_7") (pintype "passive"))
    )
    (net (code "92") (name "/PL7") (class "Default")
      (node (ref "IC3") (pin "42") (pinfunction "PL7_42") (pintype "bidirectional"))
      (node (ref "PL") (pin "8") (pinfunction "8_8") (pintype "passive"))
    )
    (net (code "93") (name "/RESET") (class "Default")
      (node (ref "C10") (pin "2") (pinfunction "2_2") (pintype "passive"))
      (node (ref "IC3") (pin "30") (pinfunction "RESET_30") (pintype "input"))
      (node (ref "PROGRAM") (pin "5") (pinfunction "5_5") (pintype "passive"))
      (node (ref "R4") (pin "2") (pinfunction "2_2") (pintype "passive"))
      (node (ref "RESET") (pin "3") (pinfunction "3_3") (pintype "passive"))
      (node (ref "RESET") (pin "4") (pinfunction "4_4") (pintype "passive"))
    )
    (net (code "94") (name "/RTS") (class "Default")
      (node (ref "BLUETOOTH") (pin "6") (pinfunction "6_6") (pintype "passive"))
    )
    (net (code "95") (name "/XCL") (class "Default")
      (node (ref "MPU") (pin "6") (pinfunction "6_6") (pintype "passive"))
    )
    (net (code "96") (name "/XDA") (class "Default")
      (node (ref "MPU") (pin "5") (pinfunction "5_5") (pintype "passive"))
    )
    (net (code "97") (name "/XTAL1") (class "Default")
      (node (ref "C4") (pin "1") (pinfunction "1_1") (pintype "passive"))
      (node (ref "Q1") (pin "2") (pinfunction "2_2") (pintype "passive"))
      (node (ref "R2") (pin "2") (pinfunction "2_2") (pintype "passive"))
      (node (ref "R3") (pin "1") (pinfunction "1_1") (pintype "passive"))
      (node (ref "Y1") (pin "3") (pinfunction "3_3") (pintype "passive"))
    )
    (net (code "98") (name "/XTAL1R") (class "Default")
      (node (ref "IC3") (pin "34") (pinfunction "XTAL1_34") (pintype "input"))
      (node (ref "R3") (pin "2") (pinfunction "2_2") (pintype "passive"))
    )
    (net (code "99") (name "/XTAL2") (class "Default")
      (node (ref "C5") (pin "1") (pinfunction "1_1") (pintype "passive"))
      (node (ref "IC3") (pin "33") (pinfunction "XTAL2_33") (pintype "output"))
      (node (ref "Q1") (pin "1") (pinfunction "1_1") (pintype "passive"))
      (node (ref "R2") (pin "1") (pinfunction "1_1") (pintype "passive"))
      (node (ref "Y1") (pin "1") (pinfunction "1_1") (pintype "passive"))
    )
    (net (code "100") (name "5.0V") (class "Default")
      (node (ref "C15") (pin "1") (pinfunction "1_1") (pintype "passive"))
      (node (ref "IC6") (pin "3") (pinfunction "VO_3") (pintype "passive"))
      (node (ref "Q2") (pin "3") (pinfunction "C_3") (pintype "passive"))
      (node (ref "Q3") (pin "3") (pinfunction "C_3") (pintype "passive"))
      (node (ref "Q4") (pin "3") (pinfunction "C_3") (pintype "passive"))
    )
    (net (code "101") (name "5V") (class "Default")
      (node (ref "C12") (pin "1") (pinfunction "1_1") (pintype "passive"))
      (node (ref "IC5") (pin "3") (pinfunction "VO_3") (pintype "passive"))
      (node (ref "SERV01") (pin "2") (pinfunction "2_2") (pintype "passive"))
      (node (ref "SERV02") (pin "2") (pinfunction "2_2") (pintype "passive"))
      (node (ref "SERV03") (pin "2") (pinfunction "2_2") (pintype "passive"))
    )
    (net (code "102") (name "GND_") (class "Default")
      (node (ref "BLUETOOTH") (pin "1") (pinfunction "1_1") (pintype "passive"))
      (node (ref "BLUETOOTH") (pin "2") (pinfunction "2_2") (pintype "passive"))
      (node (ref "BLUETOOTH") (pin "7") (pinfunction "7_7") (pintype "passive"))
      (node (ref "C1") (pin "2") (pinfunction "2_2") (pintype "passive"))
      (node (ref "C10") (pin "1") (pinfunction "1_1") (pintype "passive"))
      (node (ref "C11") (pin "2") (pinfunction "2_2") (pintype "passive"))
      (node (ref "C12") (pin "2") (pinfunction "2_2") (pintype "passive"))
      (node (ref "C13") (pin "2") (pinfunction "2_2") (pintype "passive"))
      (node (ref "C14") (pin "2") (pinfunction "2_2") (pintype "passive"))
      (node (ref "C15") (pin "2") (pinfunction "2_2") (pintype "passive"))
      (node (ref "C2") (pin "2") (pinfunction "2_2") (pintype "passive"))
      (node (ref "C3") (pin "2") (pinfunction "2_2") (pintype "passive"))
      (node (ref "C4") (pin "2") (pinfunction "2_2") (pintype "passive"))
      (node (ref "C5") (pin "2") (pinfunction "2_2") (pintype "passive"))
      (node (ref "C6") (pin "2") (pinfunction "2_2") (pintype "passive"))
      (node (ref "C7") (pin "2") (pinfunction "2_2") (pintype "passive"))
      (node (ref "C8") (pin "2") (pinfunction "2_2") (pintype "passive"))
      (node (ref "C9") (pin "2") (pinfunction "2_2") (pintype "passive"))
      (node (ref "IC1") (pin "1") (pinfunction "GND/ADJ_1") (pintype "input"))
      (node (ref "IC2") (pin "1") (pinfunction "ADJ_1") (pintype "input"))
      (node (ref "IC3") (pin "11") (pinfunction "GND_11") (pintype "power_in"))
      (node (ref "IC3") (pin "32") (pinfunction "GND1_32") (pintype "power_in"))
      (node (ref "IC3") (pin "62") (pinfunction "GND2_62") (pintype "power_in"))
      (node (ref "IC3") (pin "81") (pinfunction "GND3_81") (pintype "power_in"))
      (node (ref "IC3") (pin "99") (pinfunction "AGND_99") (pintype "power_in"))
      (node (ref "IC4") (pin "2") (pinfunction "GND_2") (pintype "power_in"))
      (node (ref "IC5") (pin "2") (pinfunction "GND_2") (pintype "passive"))
      (node (ref "IC6") (pin "2") (pinfunction "GND_2") (pintype "passive"))
      (node (ref "J1") (pin "GND") (pinfunction "GND_GND") (pintype "bidirectional"))
      (node (ref "J1") (pin "GNDBREAK") (pinfunction "GNDBREAK_GNDBREAK") (pintype "bidirectional"))
      (node (ref "LED1") (pin "2") (pinfunction "2_2") (pintype "passive"))
      (node (ref "LED2") (pin "2") (pinfunction "2_2") (pintype "passive"))
      (node (ref "LED3") (pin "2") (pinfunction "2_2") (pintype "passive"))
      (node (ref "MPU") (pin "2") (pinfunction "2_2") (pintype "passive"))
      (node (ref "MPU") (pin "7") (pinfunction "7_7") (pintype "passive"))
      (node (ref "ON") (pin "K") (pinfunction "C_K") (pintype "passive"))
      (node (ref "PROGRAM") (pin "6") (pinfunction "6_6") (pintype "passive"))
      (node (ref "R13") (pin "1") (pinfunction "1_1") (pintype "passive"))
      (node (ref "R14") (pin "1") (pinfunction "1_1") (pintype "passive"))
      (node (ref "R15") (pin "1") (pinfunction "1_1") (pintype "passive"))
      (node (ref "RESET") (pin "1") (pinfunction "1_1") (pintype "passive"))
      (node (ref "RESET") (pin "2") (pinfunction "2_2") (pintype "passive"))
      (node (ref "SERV01") (pin "3") (pinfunction "3_3") (pintype "passive"))
      (node (ref "SERV02") (pin "3") (pinfunction "3_3") (pintype "passive"))
      (node (ref "SERV03") (pin "3") (pinfunction "3_3") (pintype "passive"))
      (node (ref "TMP102") (pin "1") (pinfunction "1_1") (pintype "passive"))
      (node (ref "TMP102") (pin "6") (pinfunction "6_6") (pintype "passive"))
      (node (ref "Y1") (pin "2") (pinfunction "2_2") (pintype "passive"))
    )
    (net (code "103") (name "Net-(D1-PadA)") (class "Default")
      (node (ref "D1") (pin "A") (pinfunction "A_A") (pintype "passive"))
      (node (ref "J1") (pin "PWR") (pinfunction "PWR_PWR") (pintype "bidirectional"))
    )
    (net (code "104") (name "Net-(ON-PadA)") (class "Default")
      (node (ref "ON") (pin "A") (pinfunction "A_A") (pintype "passive"))
      (node (ref "R1") (pin "2") (pinfunction "2_2") (pintype "passive"))
    )
    (net (code "105") (name "Net-(Q2-E)") (class "Default")
      (node (ref "LED3") (pin "1") (pinfunction "1_1") (pintype "passive"))
      (node (ref "Q2") (pin "1") (pinfunction "E_1") (pintype "passive"))
    )
    (net (code "106") (name "Net-(Q3-E)") (class "Default")
      (node (ref "LED1") (pin "1") (pinfunction "1_1") (pintype "passive"))
      (node (ref "Q3") (pin "1") (pinfunction "E_1") (pintype "passive"))
    )
    (net (code "107") (name "Net-(Q4-E)") (class "Default")
      (node (ref "LED2") (pin "1") (pinfunction "1_1") (pintype "passive"))
      (node (ref "Q4") (pin "1") (pinfunction "E_1") (pintype "passive"))
    )
    (net (code "108") (name "VCC") (class "Default")
      (node (ref "C1") (pin "1") (pinfunction "1_1") (pintype "passive"))
      (node (ref "C13") (pin "1") (pinfunction "1_1") (pintype "passive"))
      (node (ref "C14") (pin "1") (pinfunction "1_1") (pintype "passive"))
      (node (ref "C2") (pin "1") (pinfunction "1_1") (pintype "passive"))
      (node (ref "D1") (pin "C") (pinfunction "C_C") (pintype "passive"))
      (node (ref "IC1") (pin "3") (pinfunction "IN_3") (pintype "input"))
      (node (ref "IC2") (pin "3") (pinfunction "VI_3") (pintype "input"))
      (node (ref "IC5") (pin "1") (pinfunction "VI_1") (pintype "input"))
      (node (ref "IC6") (pin "1") (pinfunction "VI_1") (pintype "input"))
    )
    (net (code "109") (name "unconnected-(IC4-NC{slash}FB-Pad4)") (class "Default")
      (node (ref "IC4") (pin "4") (pinfunction "NC/FB_4") (pintype "passive"))
    )
  )
)
